# v3b_pcb.net
KiCad netlist of a schematic drawn in EAGLE
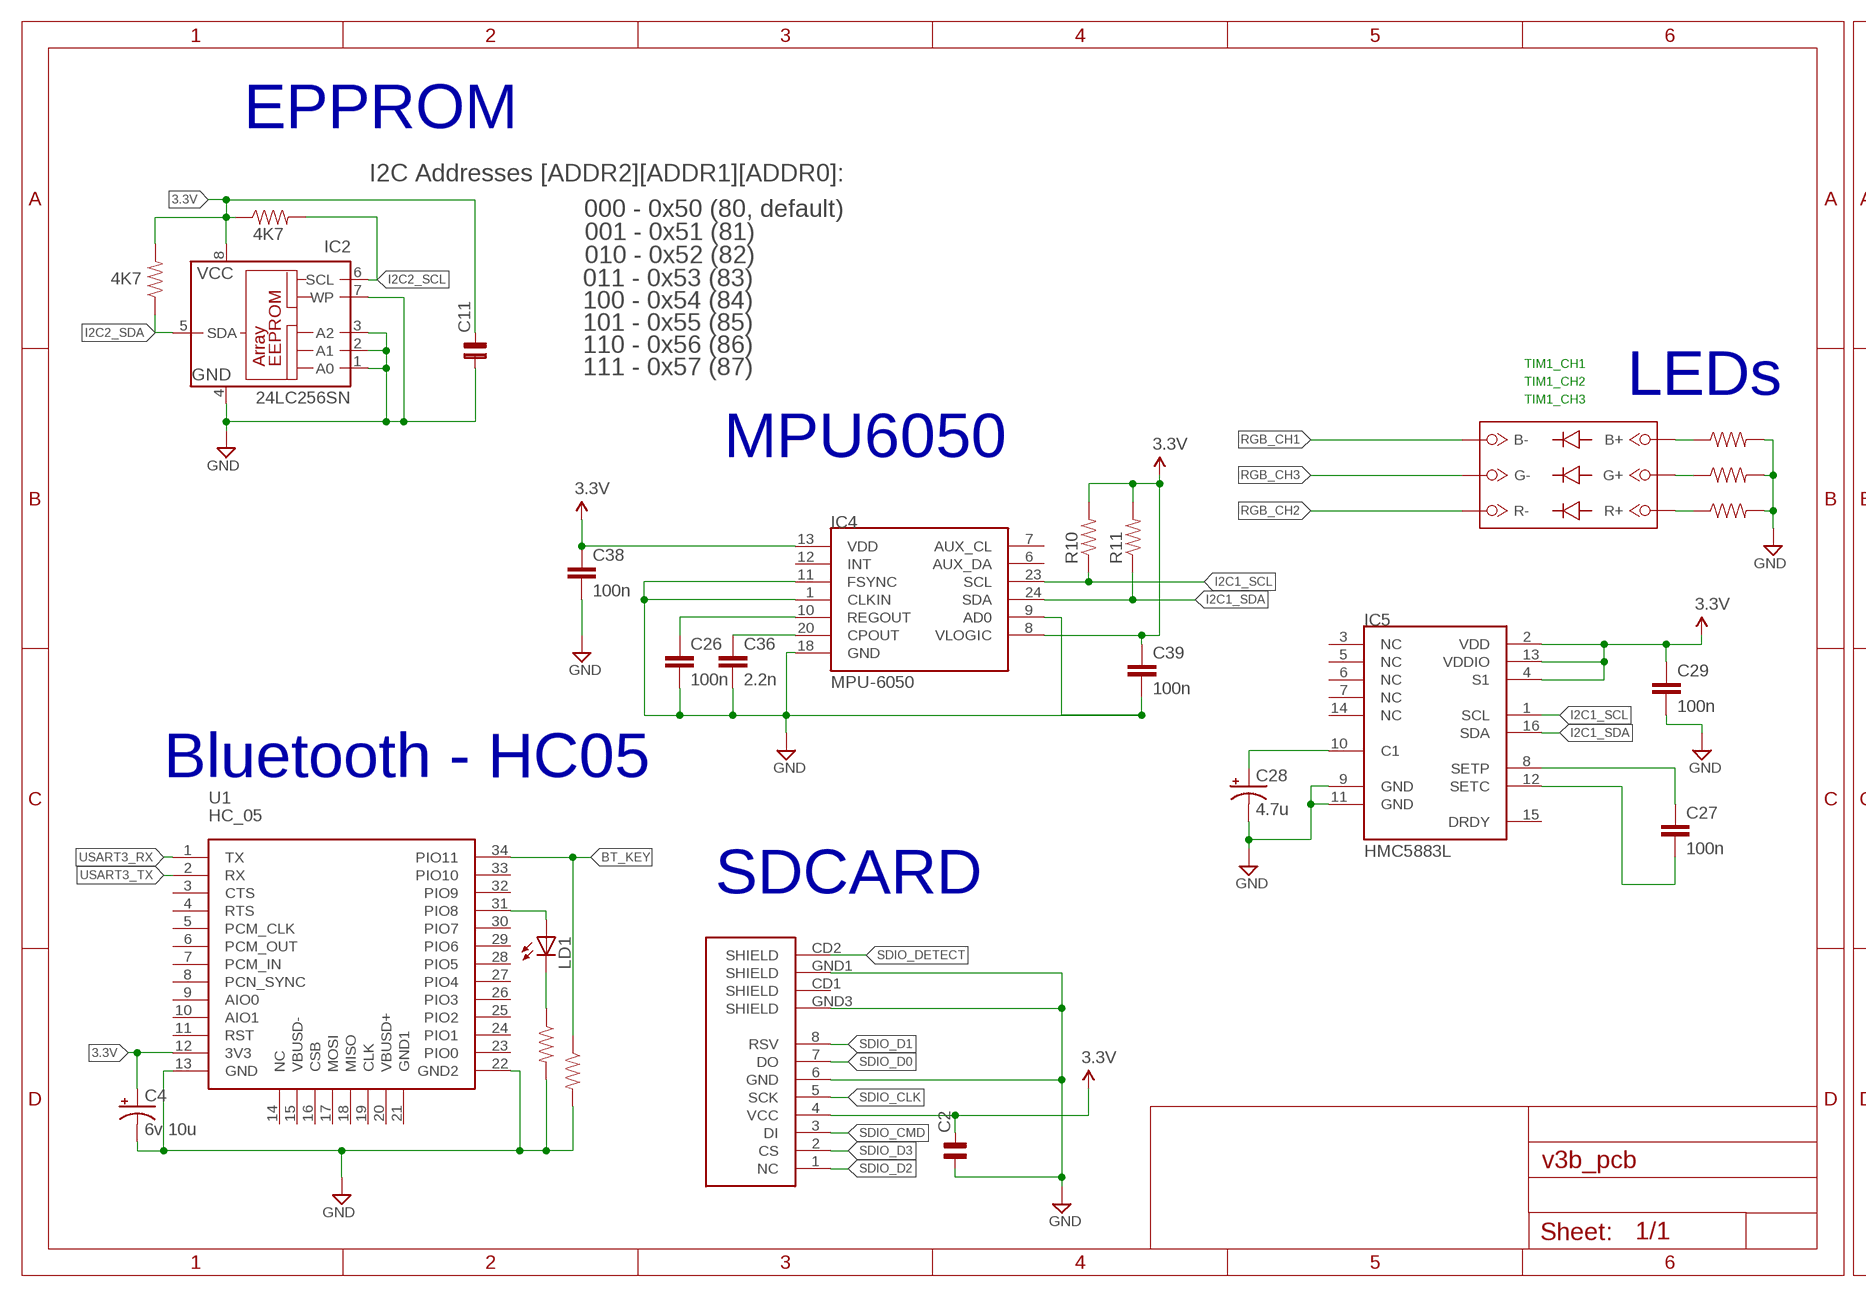
[diagram p0: schematic, sheet 1, part 1 of 2]
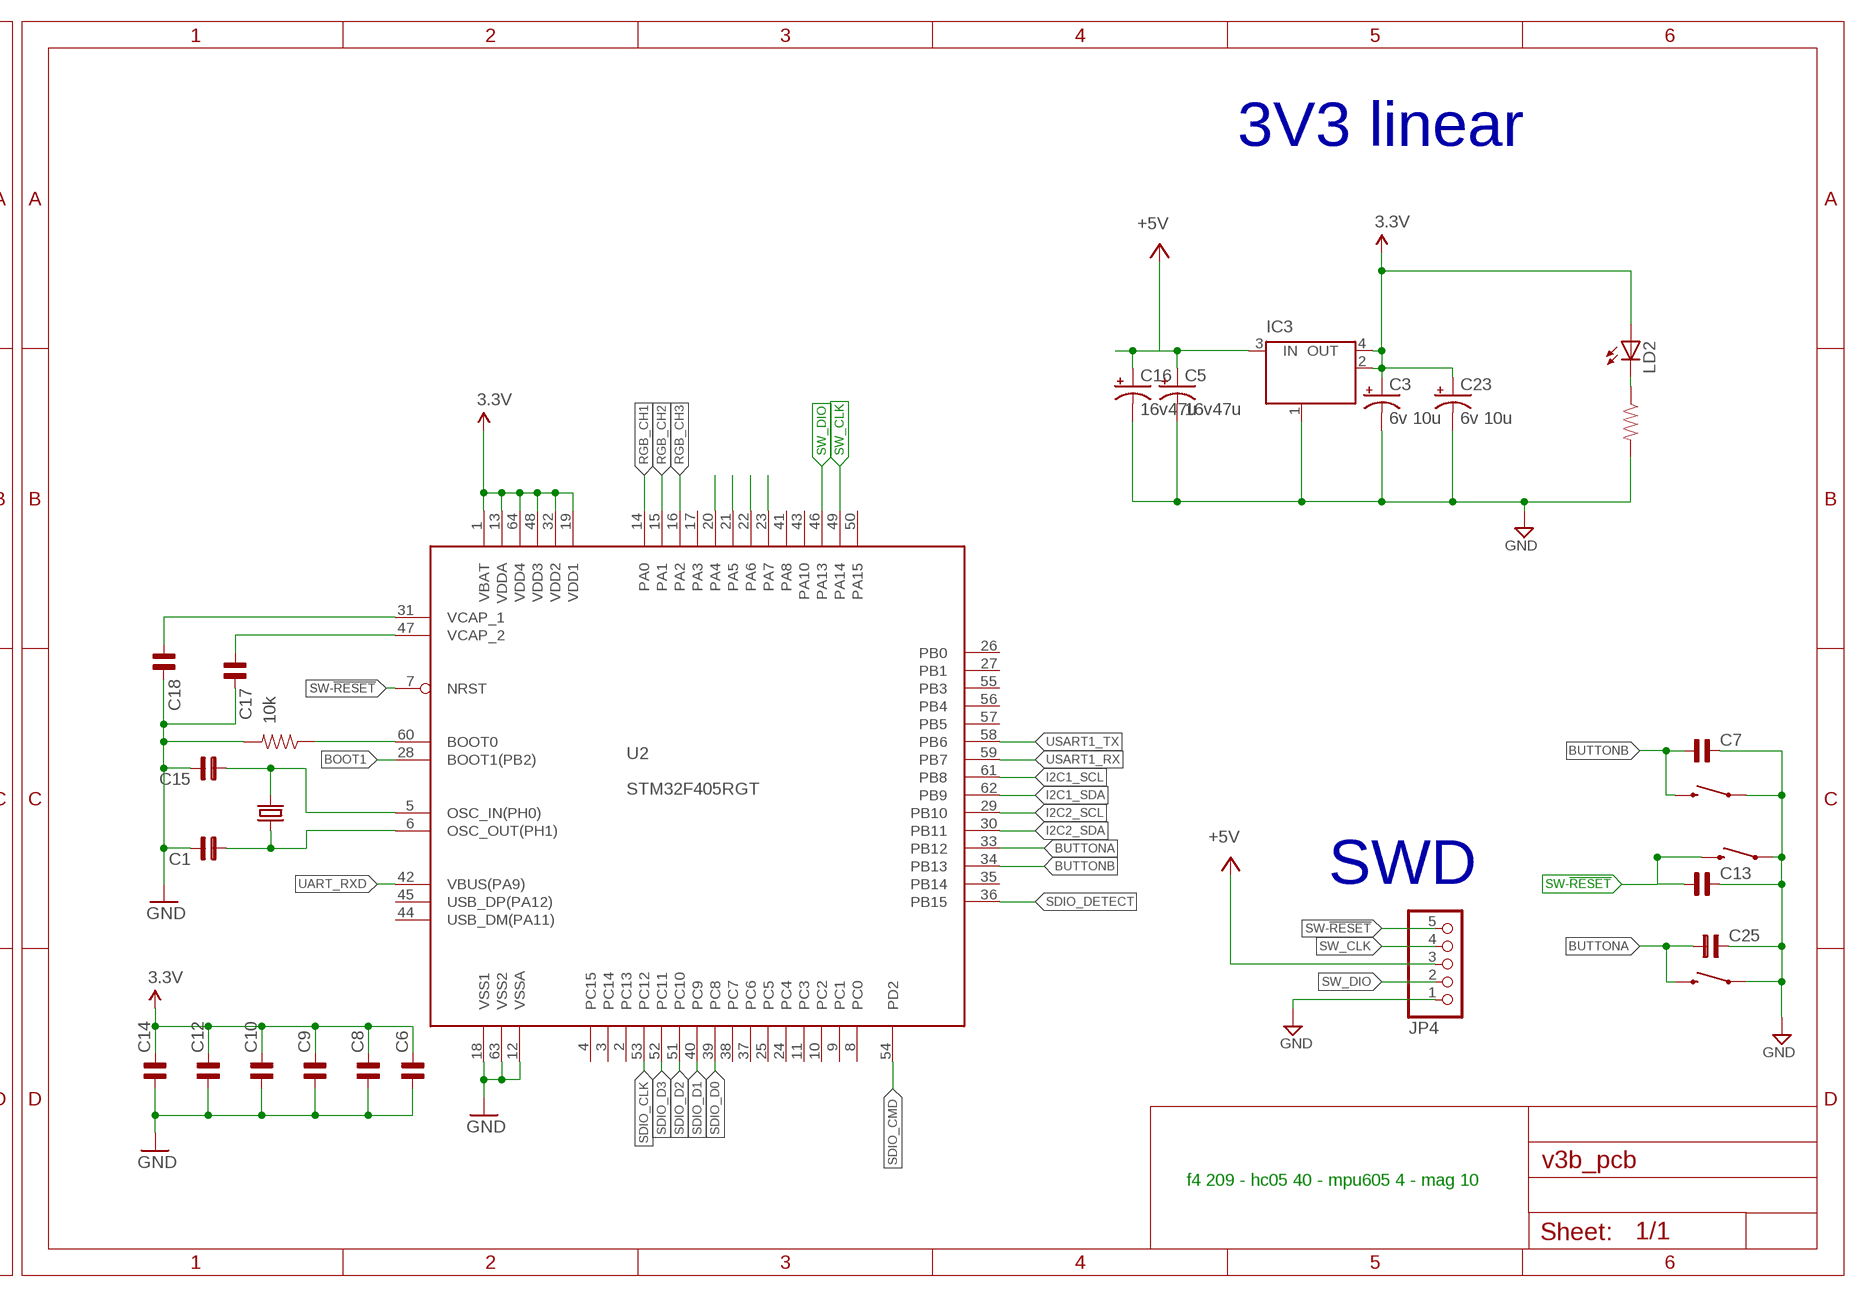
[diagram p1: schematic, sheet 1, part 2 of 2]

(export (version "E")
  (design (tool "Eeschema 10.0.6"))
  (components
    (comp (ref "C1")
      (value "C-NP-SMD-0603")
      (footprint "eagle-import:C-0603")
      (libsource (lib "eagle-import") (part "C-NP-SMD-0603"))
    )
    (comp (ref "C2")
      (value "C-NP-SMD-0603")
      (footprint "eagle-import:C-0603")
      (libsource (lib "eagle-import") (part "C-NP-SMD-0603"))
    )
    (comp (ref "C3")
      (value "6v 10u")
      (footprint "eagle-import:SMC_C")
      (libsource (lib "eagle-import") (part "CPOL-USSMCC"))
    )
    (comp (ref "C4")
      (value "6v 10u")
      (footprint "eagle-import:SMC_A")
      (libsource (lib "eagle-import") (part "CPOL-USSMCA"))
    )
    (comp (ref "C5")
      (value "16v47u")
      (footprint "eagle-import:SMC_C")
      (libsource (lib "eagle-import") (part "CPOL-USSMCC"))
    )
    (comp (ref "C6")
      (value "C-NP-SMD-0603")
      (footprint "eagle-import:C-0603")
      (libsource (lib "eagle-import") (part "C-NP-SMD-0603"))
    )
    (comp (ref "C7")
      (value "C-NP-SMD-0603")
      (footprint "eagle-import:C-0603")
      (libsource (lib "eagle-import") (part "C-NP-SMD-0603"))
    )
    (comp (ref "C8")
      (value "C-NP-SMD-0603")
      (footprint "eagle-import:C-0603")
      (libsource (lib "eagle-import") (part "C-NP-SMD-0603"))
    )
    (comp (ref "C9")
      (value "C-NP-SMD-0603")
      (footprint "eagle-import:C-0603")
      (libsource (lib "eagle-import") (part "C-NP-SMD-0603"))
    )
    (comp (ref "C10")
      (value "C-NP-SMD-0603")
      (footprint "eagle-import:C-0603")
      (libsource (lib "eagle-import") (part "C-NP-SMD-0603"))
    )
    (comp (ref "C11")
      (value "C-NP-SMD-0603")
      (footprint "eagle-import:C-0603")
      (libsource (lib "eagle-import") (part "C-NP-SMD-0603"))
    )
    (comp (ref "C12")
      (value "C-NP-SMD-0603")
      (footprint "eagle-import:C-0603")
      (libsource (lib "eagle-import") (part "C-NP-SMD-0603"))
    )
    (comp (ref "C13")
      (value "C-NP-SMD-0603")
      (footprint "eagle-import:C-0603")
      (libsource (lib "eagle-import") (part "C-NP-SMD-0603"))
    )
    (comp (ref "C14")
      (value "C-NP-SMD-0603")
      (footprint "eagle-import:C-0603")
      (libsource (lib "eagle-import") (part "C-NP-SMD-0603"))
    )
    (comp (ref "C15")
      (value "C-NP-SMD-0603")
      (footprint "eagle-import:C-0603")
      (libsource (lib "eagle-import") (part "C-NP-SMD-0603"))
    )
    (comp (ref "C16")
      (value "16v47u")
      (footprint "eagle-import:SMC_C")
      (libsource (lib "eagle-import") (part "CPOL-USSMCC"))
    )
    (comp (ref "C17")
      (value "C-NP-SMD-0603")
      (footprint "eagle-import:C-0603")
      (libsource (lib "eagle-import") (part "C-NP-SMD-0603"))
    )
    (comp (ref "C18")
      (value "C-NP-SMD-0603")
      (footprint "eagle-import:C-0603")
      (libsource (lib "eagle-import") (part "C-NP-SMD-0603"))
    )
    (comp (ref "C23")
      (value "6v 10u")
      (footprint "eagle-import:SMC_C")
      (libsource (lib "eagle-import") (part "CPOL-USSMCC"))
    )
    (comp (ref "C25")
      (value "C-NP-SMD-0603")
      (footprint "eagle-import:C-0603")
      (libsource (lib "eagle-import") (part "C-NP-SMD-0603"))
    )
    (comp (ref "C26")
      (value "100n")
      (footprint "eagle-import:SPARKFUN_0603-CAP")
      (libsource (lib "eagle-import") (part "SPARKFUN_CAP0603-CAP"))
    )
    (comp (ref "C27")
      (value "100n")
      (footprint "eagle-import:SPARKFUN_0603-CAP")
      (libsource (lib "eagle-import") (part "SPARKFUN_CAP0603-CAP"))
    )
    (comp (ref "C28")
      (value "4.7u")
      (footprint "eagle-import:SMC_A")
      (libsource (lib "eagle-import") (part "CPOL-USSMCA"))
    )
    (comp (ref "C29")
      (value "100n")
      (footprint "eagle-import:SPARKFUN_0603-CAP")
      (libsource (lib "eagle-import") (part "SPARKFUN_CAP0603-CAP"))
    )
    (comp (ref "C36")
      (value "2.2n")
      (footprint "eagle-import:SPARKFUN_0603-CAP")
      (libsource (lib "eagle-import") (part "SPARKFUN_CAP0603-CAP"))
    )
    (comp (ref "C38")
      (value "100n")
      (footprint "eagle-import:SPARKFUN_0603-CAP")
      (libsource (lib "eagle-import") (part "SPARKFUN_CAP0603-CAP"))
    )
    (comp (ref "C39")
      (value "100n")
      (footprint "eagle-import:SPARKFUN_0603-CAP")
      (libsource (lib "eagle-import") (part "SPARKFUN_CAP0603-CAP"))
    )
    (comp (ref "IC2")
      (value "24LC256SN")
      (footprint "eagle-import:SO-08")
      (fields (field (name "MF") "MICROCHIP") (field (name "MPN") "24LC256-I/SN"))
      (libsource (lib "eagle-import") (part "24SNLC256"))
    )
    (comp (ref "IC3")
      (value "LINEAR_MC33269ST-3.3T3")
      (footprint "eagle-import:LINEAR_SOT223")
      (libsource (lib "eagle-import") (part "LINEAR_MC33269ST-3.3T3"))
    )
    (comp (ref "IC4")
      (value "MPU-6050")
      (footprint "eagle-import:TESTING_QFN-24-4MM2")
      (libsource (lib "eagle-import") (part "TESTING_MPU-6050-1"))
    )
    (comp (ref "IC5")
      (value "HMC5883L")
      (footprint "eagle-import:SPARKFUN_16LPCC")
      (libsource (lib "eagle-import") (part "SPARKFUN_HMC5883LSMD"))
    )
    (comp (ref "JP4")
      (value "PINHD-1X5_2.54-90°")
      (footprint "eagle-import:1X05_90")
      (libsource (lib "eagle-import") (part "PINHD-1X5_2.54-90°"))
    )
    (comp (ref "LD1")
      (value "LEDCHIPLED_0603")
      (footprint "eagle-import:CHIPLED_0603")
      (libsource (lib "eagle-import") (part "LEDCHIPLED_0603"))
    )
    (comp (ref "LD2")
      (value "LEDCHIPLED_0603")
      (footprint "eagle-import:CHIPLED_0603")
      (libsource (lib "eagle-import") (part "LEDCHIPLED_0603"))
    )
    (comp (ref "R1")
      (value "10K")
      (footprint "eagle-import:SPARKFUN_0603-RES")
      (libsource (lib "eagle-import") (part "Robotech_RCL_SPARKFUN_RESISTOR0603-RES"))
    )
    (comp (ref "R2")
      (value "10K")
      (footprint "eagle-import:SPARKFUN_0603-RES")
      (libsource (lib "eagle-import") (part "Robotech_RCL_SPARKFUN_RESISTOR0603-RES"))
    )
    (comp (ref "R3")
      (value "10K")
      (footprint "eagle-import:SPARKFUN_0603-RES")
      (libsource (lib "eagle-import") (part "Robotech_RCL_SPARKFUN_RESISTOR0603-RES"))
    )
    (comp (ref "R5")
      (value "10K")
      (footprint "eagle-import:SPARKFUN_0603-RES")
      (libsource (lib "eagle-import") (part "Robotech_RCL_SPARKFUN_RESISTOR0603-RES"))
    )
    (comp (ref "R6")
      (value "10K")
      (footprint "eagle-import:SPARKFUN_0603-RES")
      (libsource (lib "eagle-import") (part "Robotech_RCL_SPARKFUN_RESISTOR0603-RES"))
    )
    (comp (ref "R7")
      (value "10k")
      (footprint "eagle-import:SPARKFUN_0603-RES")
      (libsource (lib "eagle-import") (part "Robotech_RCL_SPARKFUN_RESISTOR0603-RES"))
    )
    (comp (ref "R9")
      (value "10K")
      (footprint "eagle-import:SPARKFUN_0603-RES")
      (libsource (lib "eagle-import") (part "Robotech_RCL_SPARKFUN_RESISTOR0603-RES"))
    )
    (comp (ref "R10")
      (value "SPARKFUN_RESISTOR0603-RES")
      (footprint "eagle-import:SPARKFUN_0603-RES")
      (libsource (lib "eagle-import") (part "SPARKFUN_RESISTOR0603-RES"))
    )
    (comp (ref "R11")
      (value "SPARKFUN_RESISTOR0603-RES")
      (footprint "eagle-import:SPARKFUN_0603-RES")
      (libsource (lib "eagle-import") (part "SPARKFUN_RESISTOR0603-RES"))
    )
    (comp (ref "R15")
      (value "4K7")
      (footprint "eagle-import:SPARKFUN_0603-RES")
      (libsource (lib "eagle-import") (part "Robotech_RCL_SPARKFUN_RESISTOR0603-RES"))
    )
    (comp (ref "R16")
      (value "4K7")
      (footprint "eagle-import:SPARKFUN_0603-RES")
      (libsource (lib "eagle-import") (part "Robotech_RCL_SPARKFUN_RESISTOR0603-RES"))
    )
    (comp (ref "S1")
      (value "RESET")
      (footprint "eagle-import:TACTILE-SWITCH-1101NE")
      (fields (field (name "PARTNO") "EVQ-P7J01P"))
      (libsource (lib "eagle-import") (part "SWITCH-MOMENTARY-2-SMD-1101NE"))
    )
    (comp (ref "S2")
      (value "RESET")
      (footprint "eagle-import:TACTILE-SWITCH-1101NE")
      (fields (field (name "PARTNO") "EVQ-P7J01P"))
      (libsource (lib "eagle-import") (part "SWITCH-MOMENTARY-2-SMD-1101NE"))
    )
    (comp (ref "S4")
      (value "RESET")
      (footprint "eagle-import:TACTILE-SWITCH-1101NE")
      (fields (field (name "PARTNO") "EVQ-P7J01P"))
      (libsource (lib "eagle-import") (part "SWITCH-MOMENTARY-2-SMD-1101NE"))
    )
    (comp (ref "SDCARD2")
      (value "microSD Socket")
      (footprint "eagle-import:MICRO-SD-SOCKET-PP")
      (libsource (lib "eagle-import") (part "USD-SOCKETNEW"))
    )
    (comp (ref "U$12")
      (value "RGB_LED")
      (footprint "eagle-import:SMD")
      (libsource (lib "eagle-import") (part "RGB_LED"))
    )
    (comp (ref "U1")
      (value "HC_05")
      (footprint "eagle-import:BLUETOOTH_SMD")
      (libsource (lib "eagle-import") (part "HC_05"))
    )
    (comp (ref "U2")
      (value "STM32F405RGT")
      (footprint "eagle-import:LQFP64")
      (libsource (lib "eagle-import") (part "STM32F405RGT"))
    )
    (comp (ref "Y2")
      (value "CRYSTALHC49US")
      (footprint "eagle-import:HC49US")
      (libsource (lib "eagle-import") (part "CRYSTALHC49US"))
    )
  )
  (nets
    (net (code "1") (name "+5V") (class "Default")
      (node (ref "C16") (pin "+") (pinfunction "+_+") (pintype "passive"))
      (node (ref "C5") (pin "+") (pinfunction "+_+") (pintype "passive"))
      (node (ref "IC3") (pin "3") (pinfunction "IN_3") (pintype "input"))
      (node (ref "JP4") (pin "3") (pinfunction "3_3") (pintype "passive"))
    )
    (net (code "2") (name "/SW-~{RESET}") (class "Default")
      (node (ref "C13") (pin "1") (pinfunction "1_1") (pintype "passive"))
      (node (ref "JP4") (pin "5") (pinfunction "5_5") (pintype "passive"))
      (node (ref "S1") (pin "P$2") (pinfunction "2_P$2") (pintype "passive"))
      (node (ref "U2") (pin "7") (pinfunction "NRST_7") (pintype "input"))
    )
    (net (code "3") (name "3.3V") (class "Default")
      (node (ref "C10") (pin "2") (pinfunction "2_2") (pintype "passive"))
      (node (ref "C11") (pin "2") (pinfunction "2_2") (pintype "passive"))
      (node (ref "C12") (pin "2") (pinfunction "2_2") (pintype "passive"))
      (node (ref "C14") (pin "2") (pinfunction "2_2") (pintype "passive"))
      (node (ref "C2") (pin "2") (pinfunction "2_2") (pintype "passive"))
      (node (ref "C23") (pin "+") (pinfunction "+_+") (pintype "passive"))
      (node (ref "C29") (pin "1") (pinfunction "1_1") (pintype "passive"))
      (node (ref "C3") (pin "+") (pinfunction "+_+") (pintype "passive"))
      (node (ref "C38") (pin "1") (pinfunction "1_1") (pintype "passive"))
      (node (ref "C39") (pin "1") (pinfunction "1_1") (pintype "passive"))
      (node (ref "C4") (pin "+") (pinfunction "+_+") (pintype "passive"))
      (node (ref "C6") (pin "2") (pinfunction "2_2") (pintype "passive"))
      (node (ref "C8") (pin "2") (pinfunction "2_2") (pintype "passive"))
      (node (ref "C9") (pin "2") (pinfunction "2_2") (pintype "passive"))
      (node (ref "IC2") (pin "8") (pinfunction "VCC_8") (pintype "power_in"))
      (node (ref "IC3") (pin "2") (pinfunction "OUT_2") (pintype "passive"))
      (node (ref "IC3") (pin "4") (pinfunction "OUT_4") (pintype "passive"))
      (node (ref "IC4") (pin "13") (pinfunction "VDD_13") (pintype "bidirectional"))
      (node (ref "IC4") (pin "8") (pinfunction "VLOGIC_8") (pintype "bidirectional"))
      (node (ref "IC5") (pin "13") (pinfunction "VDDIO_13") (pintype "bidirectional"))
      (node (ref "IC5") (pin "2") (pinfunction "VDD_2") (pintype "bidirectional"))
      (node (ref "IC5") (pin "4") (pinfunction "S1_4") (pintype "bidirectional"))
      (node (ref "LD2") (pin "A") (pinfunction "A_A") (pintype "passive"))
      (node (ref "R10") (pin "2") (pinfunction "2_2") (pintype "passive"))
      (node (ref "R11") (pin "2") (pinfunction "2_2") (pintype "passive"))
      (node (ref "R15") (pin "1") (pinfunction "1_1") (pintype "passive"))
      (node (ref "R16") (pin "2") (pinfunction "2_2") (pintype "passive"))
      (node (ref "SDCARD2") (pin "4") (pinfunction "VCC_4") (pintype "bidirectional"))
      (node (ref "U1") (pin "12") (pinfunction "3V3_12") (pintype "bidirectional"))
      (node (ref "U2") (pin "1") (pinfunction "VBAT_1") (pintype "power_in"))
      (node (ref "U2") (pin "13") (pinfunction "VDDA_13") (pintype "power_in"))
      (node (ref "U2") (pin "19") (pinfunction "VDD1_19") (pintype "power_in"))
      (node (ref "U2") (pin "32") (pinfunction "VDD2_32") (pintype "power_in"))
      (node (ref "U2") (pin "48") (pinfunction "VDD3_48") (pintype "power_in"))
      (node (ref "U2") (pin "64") (pinfunction "VDD4_64") (pintype "power_in"))
    )
    (net (code "4") (name "BOOT1") (class "Default")
      (node (ref "U2") (pin "28") (pinfunction "BOOT1(PB2)_28") (pintype "input"))
    )
    (net (code "5") (name "BT_KEY") (class "Default")
      (node (ref "R5") (pin "1") (pinfunction "1_1") (pintype "passive"))
      (node (ref "U1") (pin "34") (pinfunction "PIO11_34") (pintype "bidirectional"))
    )
    (net (code "6") (name "BUTTONA") (class "Default")
      (node (ref "C25") (pin "1") (pinfunction "1_1") (pintype "passive"))
      (node (ref "S2") (pin "P$2") (pinfunction "2_P$2") (pintype "passive"))
      (node (ref "U2") (pin "33") (pinfunction "PB12_33") (pintype "bidirectional"))
    )
    (net (code "7") (name "BUTTONB") (class "Default")
      (node (ref "C7") (pin "1") (pinfunction "1_1") (pintype "passive"))
      (node (ref "S4") (pin "P$2") (pinfunction "2_P$2") (pintype "passive"))
      (node (ref "U2") (pin "34") (pinfunction "PB13_34") (pintype "bidirectional"))
    )
    (net (code "8") (name "GND") (class "Default")
      (node (ref "C1") (pin "2") (pinfunction "2_2") (pintype "passive"))
      (node (ref "C10") (pin "1") (pinfunction "1_1") (pintype "passive"))
      (node (ref "C11") (pin "1") (pinfunction "1_1") (pintype "passive"))
      (node (ref "C12") (pin "1") (pinfunction "1_1") (pintype "passive"))
      (node (ref "C13") (pin "2") (pinfunction "2_2") (pintype "passive"))
      (node (ref "C14") (pin "1") (pinfunction "1_1") (pintype "passive"))
      (node (ref "C15") (pin "2") (pinfunction "2_2") (pintype "passive"))
      (node (ref "C16") (pin "-") (pinfunction "-_-") (pintype "passive"))
      (node (ref "C17") (pin "2") (pinfunction "2_2") (pintype "passive"))
      (node (ref "C18") (pin "2") (pinfunction "2_2") (pintype "passive"))
      (node (ref "C2") (pin "1") (pinfunction "1_1") (pintype "passive"))
      (node (ref "C23") (pin "-") (pinfunction "-_-") (pintype "passive"))
      (node (ref "C25") (pin "2") (pinfunction "2_2") (pintype "passive"))
      (node (ref "C26") (pin "2") (pinfunction "2_2") (pintype "passive"))
      (node (ref "C28") (pin "-") (pinfunction "-_-") (pintype "passive"))
      (node (ref "C29") (pin "2") (pinfunction "2_2") (pintype "passive"))
      (node (ref "C3") (pin "-") (pinfunction "-_-") (pintype "passive"))
      (node (ref "C36") (pin "2") (pinfunction "2_2") (pintype "passive"))
      (node (ref "C38") (pin "2") (pinfunction "2_2") (pintype "passive"))
      (node (ref "C39") (pin "2") (pinfunction "2_2") (pintype "passive"))
      (node (ref "C4") (pin "-") (pinfunction "-_-") (pintype "passive"))
      (node (ref "C5") (pin "-") (pinfunction "-_-") (pintype "passive"))
      (node (ref "C6") (pin "1") (pinfunction "1_1") (pintype "passive"))
      (node (ref "C7") (pin "2") (pinfunction "2_2") (pintype "passive"))
      (node (ref "C8") (pin "1") (pinfunction "1_1") (pintype "passive"))
      (node (ref "C9") (pin "1") (pinfunction "1_1") (pintype "passive"))
      (node (ref "IC2") (pin "1") (pinfunction "A0_1") (pintype "input"))
      (node (ref "IC2") (pin "2") (pinfunction "A1_2") (pintype "input"))
      (node (ref "IC2") (pin "3") (pinfunction "A2_3") (pintype "input"))
      (node (ref "IC2") (pin "4") (pinfunction "GND_4") (pintype "power_in"))
      (node (ref "IC2") (pin "7") (pinfunction "WP_7") (pintype "input"))
      (node (ref "IC3") (pin "1") (pinfunction "GND/ADJ_1") (pintype "input"))
      (node (ref "IC4") (pin "1") (pinfunction "CLKIN_1") (pintype "bidirectional"))
      (node (ref "IC4") (pin "11") (pinfunction "FSYNC_11") (pintype "bidirectional"))
      (node (ref "IC4") (pin "18") (pinfunction "GND_18") (pintype "bidirectional"))
      (node (ref "IC4") (pin "9") (pinfunction "AD0_9") (pintype "bidirectional"))
      (node (ref "IC5") (pin "11") (pinfunction "GND_11") (pintype "bidirectional"))
      (node (ref "IC5") (pin "9") (pinfunction "GND_9") (pintype "bidirectional"))
      (node (ref "JP4") (pin "1") (pinfunction "1_1") (pintype "passive"))
      (node (ref "R1") (pin "2") (pinfunction "2_2") (pintype "passive"))
      (node (ref "R2") (pin "2") (pinfunction "2_2") (pintype "passive"))
      (node (ref "R3") (pin "2") (pinfunction "2_2") (pintype "passive"))
      (node (ref "R5") (pin "2") (pinfunction "2_2") (pintype "passive"))
      (node (ref "R6") (pin "2") (pinfunction "2_2") (pintype "passive"))
      (node (ref "R7") (pin "2") (pinfunction "2_2") (pintype "passive"))
      (node (ref "R9") (pin "2") (pinfunction "2_2") (pintype "passive"))
      (node (ref "S1") (pin "P$1") (pinfunction "1_P$1") (pintype "passive"))
      (node (ref "S2") (pin "P$1") (pinfunction "1_P$1") (pintype "passive"))
      (node (ref "S4") (pin "P$1") (pinfunction "1_P$1") (pintype "passive"))
      (node (ref "SDCARD2") (pin "6") (pinfunction "GND_6") (pintype "bidirectional"))
      (node (ref "SDCARD2") (pin "GND1") (pinfunction "SHIELD_GND1") (pintype "bidirectional"))
      (node (ref "SDCARD2") (pin "GND3") (pinfunction "SHIELD_GND3") (pintype "bidirectional"))
      (node (ref "U1") (pin "13") (pinfunction "GND_13") (pintype "bidirectional"))
      (node (ref "U1") (pin "22") (pinfunction "GND2_22") (pintype "bidirectional"))
      (node (ref "U2") (pin "12") (pinfunction "VSSA_12") (pintype "power_in"))
      (node (ref "U2") (pin "18") (pinfunction "VSS1_18") (pintype "power_in"))
      (node (ref "U2") (pin "63") (pinfunction "VSS2_63") (pintype "power_in"))
    )
    (net (code "9") (name "I2C1_SCL") (class "Default")
      (node (ref "IC4") (pin "23") (pinfunction "SCL_23") (pintype "bidirectional"))
      (node (ref "IC5") (pin "1") (pinfunction "SCL_1") (pintype "bidirectional"))
      (node (ref "R10") (pin "1") (pinfunction "1_1") (pintype "passive"))
      (node (ref "U2") (pin "61") (pinfunction "PB8_61") (pintype "bidirectional"))
    )
    (net (code "10") (name "I2C1_SDA") (class "Default")
      (node (ref "IC4") (pin "24") (pinfunction "SDA_24") (pintype "bidirectional"))
      (node (ref "IC5") (pin "16") (pinfunction "SDA_16") (pintype "bidirectional"))
      (node (ref "R11") (pin "1") (pinfunction "1_1") (pintype "passive"))
      (node (ref "U2") (pin "62") (pinfunction "PB9_62") (pintype "bidirectional"))
    )
    (net (code "11") (name "I2C2_SCL") (class "Default")
      (node (ref "IC2") (pin "6") (pinfunction "SCL_6") (pintype "input"))
      (node (ref "R15") (pin "2") (pinfunction "2_2") (pintype "passive"))
      (node (ref "U2") (pin "29") (pinfunction "PB10_29") (pintype "bidirectional"))
    )
    (net (code "12") (name "I2C2_SDA") (class "Default")
      (node (ref "IC2") (pin "5") (pinfunction "SDA_5") (pintype "bidirectional"))
      (node (ref "R16") (pin "1") (pinfunction "1_1") (pintype "passive"))
      (node (ref "U2") (pin "30") (pinfunction "PB11_30") (pintype "bidirectional"))
    )
    (net (code "13") (name "Net-(IC4-CPOUT)") (class "Default")
      (node (ref "C36") (pin "1") (pinfunction "1_1") (pintype "passive"))
      (node (ref "IC4") (pin "20") (pinfunction "CPOUT_20") (pintype "bidirectional"))
    )
    (net (code "14") (name "Net-(IC4-REGOUT)") (class "Default")
      (node (ref "C26") (pin "1") (pinfunction "1_1") (pintype "passive"))
      (node (ref "IC4") (pin "10") (pinfunction "REGOUT_10") (pintype "bidirectional"))
    )
    (net (code "15") (name "Net-(IC5-C1)") (class "Default")
      (node (ref "C28") (pin "+") (pinfunction "+_+") (pintype "passive"))
      (node (ref "IC5") (pin "10") (pinfunction "C1_10") (pintype "bidirectional"))
    )
    (net (code "16") (name "Net-(IC5-SETC)") (class "Default")
      (node (ref "C27") (pin "2") (pinfunction "2_2") (pintype "passive"))
      (node (ref "IC5") (pin "12") (pinfunction "SETC_12") (pintype "bidirectional"))
    )
    (net (code "17") (name "Net-(IC5-SETP)") (class "Default")
      (node (ref "C27") (pin "1") (pinfunction "1_1") (pintype "passive"))
      (node (ref "IC5") (pin "8") (pinfunction "SETP_8") (pintype "bidirectional"))
    )
    (net (code "18") (name "Net-(LD1-PadC)") (class "Default")
      (node (ref "LD1") (pin "C") (pinfunction "C_C") (pintype "passive"))
      (node (ref "R9") (pin "1") (pinfunction "1_1") (pintype "passive"))
    )
    (net (code "19") (name "Net-(LD2-PadC)") (class "Default")
      (node (ref "LD2") (pin "C") (pinfunction "C_C") (pintype "passive"))
      (node (ref "R1") (pin "1") (pinfunction "1_1") (pintype "passive"))
    )
    (net (code "20") (name "Net-(R2-Pad1)") (class "Default")
      (node (ref "R2") (pin "1") (pinfunction "1_1") (pintype "passive"))
      (node (ref "U$12") (pin "B+") (pinfunction "B+_B+") (pintype "bidirectional"))
    )
    (net (code "21") (name "Net-(R3-Pad1)") (class "Default")
      (node (ref "R3") (pin "1") (pinfunction "1_1") (pintype "passive"))
      (node (ref "U$12") (pin "G+") (pinfunction "G+_G+") (pintype "bidirectional"))
    )
    (net (code "22") (name "Net-(R6-Pad1)") (class "Default")
      (node (ref "R6") (pin "1") (pinfunction "1_1") (pintype "passive"))
      (node (ref "U$12") (pin "R+") (pinfunction "R+_R+") (pintype "bidirectional"))
    )
    (net (code "23") (name "Net-(U1-PIO8)") (class "Default")
      (node (ref "LD1") (pin "A") (pinfunction "A_A") (pintype "passive"))
      (node (ref "U1") (pin "31") (pinfunction "PIO8_31") (pintype "bidirectional"))
    )
    (net (code "24") (name "Net-(U2-BOOT0)") (class "Default")
      (node (ref "R7") (pin "1") (pinfunction "1_1") (pintype "passive"))
      (node (ref "U2") (pin "60") (pinfunction "BOOT0_60") (pintype "input"))
    )
    (net (code "25") (name "Net-(U2-OSC_IN(PH0))") (class "Default")
      (node (ref "C15") (pin "1") (pinfunction "1_1") (pintype "passive"))
      (node (ref "U2") (pin "5") (pinfunction "OSC_IN(PH0)_5") (pintype "bidirectional"))
      (node (ref "Y2") (pin "2") (pinfunction "2_2") (pintype "passive"))
    )
    (net (code "26") (name "Net-(U2-OSC_OUT(PH1))") (class "Default")
      (node (ref "C1") (pin "1") (pinfunction "1_1") (pintype "passive"))
      (node (ref "U2") (pin "6") (pinfunction "OSC_OUT(PH1)_6") (pintype "bidirectional"))
      (node (ref "Y2") (pin "1") (pinfunction "1_1") (pintype "passive"))
    )
    (net (code "27") (name "Net-(U2-VCAP_1)") (class "Default")
      (node (ref "C18") (pin "1") (pinfunction "1_1") (pintype "passive"))
      (node (ref "U2") (pin "31") (pinfunction "VCAP_1_31") (pintype "bidirectional"))
    )
    (net (code "28") (name "Net-(U2-VCAP_2)") (class "Default")
      (node (ref "C17") (pin "1") (pinfunction "1_1") (pintype "passive"))
      (node (ref "U2") (pin "47") (pinfunction "VCAP_2_47") (pintype "bidirectional"))
    )
    (net (code "29") (name "RGB_CH1") (class "Default")
      (node (ref "U$12") (pin "B-") (pinfunction "B-_B-") (pintype "bidirectional"))
      (node (ref "U2") (pin "14") (pinfunction "PA0_14") (pintype "bidirectional"))
    )
    (net (code "30") (name "RGB_CH2") (class "Default")
      (node (ref "U$12") (pin "R-") (pinfunction "R-_R-") (pintype "bidirectional"))
      (node (ref "U2") (pin "15") (pinfunction "PA1_15") (pintype "bidirectional"))
    )
    (net (code "31") (name "RGB_CH3") (class "Default")
      (node (ref "U$12") (pin "G-") (pinfunction "G-_G-") (pintype "bidirectional"))
      (node (ref "U2") (pin "16") (pinfunction "PA2_16") (pintype "bidirectional"))
    )
    (net (code "32") (name "SDIO_CLK") (class "Default")
      (node (ref "SDCARD2") (pin "5") (pinfunction "SCK_5") (pintype "bidirectional"))
      (node (ref "U2") (pin "53") (pinfunction "PC12_53") (pintype "bidirectional"))
    )
    (net (code "33") (name "SDIO_CMD") (class "Default")
      (node (ref "SDCARD2") (pin "3") (pinfunction "DI_3") (pintype "bidirectional"))
      (node (ref "U2") (pin "54") (pinfunction "PD2_54") (pintype "bidirectional"))
    )
    (net (code "34") (name "SDIO_D0") (class "Default")
      (node (ref "SDCARD2") (pin "7") (pinfunction "DO_7") (pintype "bidirectional"))
      (node (ref "U2") (pin "39") (pinfunction "PC8_39") (pintype "bidirectional"))
    )
    (net (code "35") (name "SDIO_D1") (class "Default")
      (node (ref "SDCARD2") (pin "8") (pinfunction "RSV_8") (pintype "bidirectional"))
      (node (ref "U2") (pin "40") (pinfunction "PC9_40") (pintype "bidirectional"))
    )
    (net (code "36") (name "SDIO_D2") (class "Default")
      (node (ref "SDCARD2") (pin "1") (pinfunction "NC_1") (pintype "bidirectional"))
      (node (ref "U2") (pin "51") (pinfunction "PC10_51") (pintype "bidirectional"))
    )
    (net (code "37") (name "SDIO_D3") (class "Default")
      (node (ref "SDCARD2") (pin "2") (pinfunction "CS_2") (pintype "bidirectional"))
      (node (ref "U2") (pin "52") (pinfunction "PC11_52") (pintype "bidirectional"))
    )
    (net (code "38") (name "SDIO_DETECT") (class "Default")
      (node (ref "SDCARD2") (pin "CD2") (pinfunction "SHIELD_CD2") (pintype "bidirectional"))
      (node (ref "U2") (pin "36") (pinfunction "PB15_36") (pintype "bidirectional"))
    )
    (net (code "39") (name "SW_CLK") (class "Default")
      (node (ref "JP4") (pin "4") (pinfunction "4_4") (pintype "passive"))
      (node (ref "U2") (pin "49") (pinfunction "PA14_49") (pintype "bidirectional"))
    )
    (net (code "40") (name "SW_DIO") (class "Default")
      (node (ref "JP4") (pin "2") (pinfunction "2_2") (pintype "passive"))
      (node (ref "U2") (pin "46") (pinfunction "PA13_46") (pintype "bidirectional"))
    )
    (net (code "41") (name "UART_RXD") (class "Default")
      (node (ref "U2") (pin "42") (pinfunction "VBUS(PA9)_42") (pintype "bidirectional"))
    )
    (net (code "42") (name "USART1_RX") (class "Default")
      (node (ref "U2") (pin "59") (pinfunction "PB7_59") (pintype "bidirectional"))
    )
    (net (code "43") (name "USART1_TX") (class "Default")
      (node (ref "U2") (pin "58") (pinfunction "PB6_58") (pintype "bidirectional"))
    )
    (net (code "44") (name "USART3_RX") (class "Default")
      (node (ref "U1") (pin "1") (pinfunction "TX_1") (pintype "bidirectional"))
    )
    (net (code "45") (name "USART3_TX") (class "Default")
      (node (ref "U1") (pin "2") (pinfunction "RX_2") (pintype "bidirectional"))
    )
    (net (code "46") (name "unconnected-(IC4-AUX_CL-Pad7)") (class "Default")
      (node (ref "IC4") (pin "7") (pinfunction "AUX_CL_7") (pintype "bidirectional"))
    )
    (net (code "47") (name "unconnected-(IC4-AUX_DA-Pad6)") (class "Default")
      (node (ref "IC4") (pin "6") (pinfunction "AUX_DA_6") (pintype "bidirectional"))
    )
    (net (code "48") (name "unconnected-(IC4-INT-Pad12)") (class "Default")
      (node (ref "IC4") (pin "12") (pinfunction "INT_12") (pintype "bidirectional"))
    )
    (net (code "49") (name "unconnected-(IC5-DRDY-Pad15)") (class "Default")
      (node (ref "IC5") (pin "15") (pinfunction "DRDY_15") (pintype "bidirectional"))
    )
    (net (code "50") (name "unconnected-(IC5-NC-Pad3)") (class "Default")
      (node (ref "IC5") (pin "3") (pinfunction "NC_3") (pintype "bidirectional"))
    )
    (net (code "51") (name "unconnected-(IC5-NC-Pad5)") (class "Default")
      (node (ref "IC5") (pin "5") (pinfunction "NC_5") (pintype "bidirectional"))
    )
    (net (code "52") (name "unconnected-(IC5-NC-Pad6)") (class "Default")
      (node (ref "IC5") (pin "6") (pinfunction "NC_6") (pintype "bidirectional"))
    )
    (net (code "53") (name "unconnected-(IC5-NC-Pad7)") (class "Default")
      (node (ref "IC5") (pin "7") (pinfunction "NC_7") (pintype "bidirectional"))
    )
    (net (code "54") (name "unconnected-(IC5-NC-Pad14)") (class "Default")
      (node (ref "IC5") (pin "14") (pinfunction "NC_14") (pintype "bidirectional"))
    )
    (net (code "55") (name "unconnected-(SDCARD2-SHIELD-PadCD1)") (class "Default")
      (node (ref "SDCARD2") (pin "CD1") (pinfunction "SHIELD_CD1") (pintype "bidirectional"))
    )
    (net (code "56") (name "unconnected-(U1-AIO0-Pad9)") (class "Default")
      (node (ref "U1") (pin "9") (pinfunction "AIO0_9") (pintype "bidirectional"))
    )
    (net (code "57") (name "unconnected-(U1-AIO1-Pad10)") (class "Default")
      (node (ref "U1") (pin "10") (pinfunction "AIO1_10") (pintype "bidirectional"))
    )
    (net (code "58") (name "unconnected-(U1-CLK-Pad19)") (class "Default")
      (node (ref "U1") (pin "19") (pinfunction "CLK_19") (pintype "bidirectional"))
    )
    (net (code "59") (name "unconnected-(U1-CSB-Pad16)") (class "Default")
      (node (ref "U1") (pin "16") (pinfunction "CSB_16") (pintype "bidirectional"))
    )
    (net (code "60") (name "unconnected-(U1-CTS-Pad3)") (class "Default")
      (node (ref "U1") (pin "3") (pinfunction "CTS_3") (pintype "bidirectional"))
    )
    (net (code "61") (name "unconnected-(U1-GND1-Pad21)") (class "Default")
      (node (ref "U1") (pin "21") (pinfunction "GND1_21") (pintype "bidirectional"))
    )
    (net (code "62") (name "unconnected-(U1-MISO-Pad18)") (class "Default")
      (node (ref "U1") (pin "18") (pinfunction "MISO_18") (pintype "bidirectional"))
    )
    (net (code "63") (name "unconnected-(U1-MOSI-Pad17)") (class "Default")
      (node (ref "U1") (pin "17") (pinfunction "MOSI_17") (pintype "bidirectional"))
    )
    (net (code "64") (name "unconnected-(U1-NC-Pad14)") (class "Default")
      (node (ref "U1") (pin "14") (pinfunction "NC_14") (pintype "bidirectional"))
    )
    (net (code "65") (name "unconnected-(U1-PCM_CLK-Pad5)") (class "Default")
      (node (ref "U1") (pin "5") (pinfunction "PCM_CLK_5") (pintype "bidirectional"))
    )
    (net (code "66") (name "unconnected-(U1-PCM_IN-Pad7)") (class "Default")
      (node (ref "U1") (pin "7") (pinfunction "PCM_IN_7") (pintype "bidirectional"))
    )
    (net (code "67") (name "unconnected-(U1-PCM_OUT-Pad6)") (class "Default")
      (node (ref "U1") (pin "6") (pinfunction "PCM_OUT_6") (pintype "bidirectional"))
    )
    (net (code "68") (name "unconnected-(U1-PCN_SYNC-Pad8)") (class "Default")
      (node (ref "U1") (pin "8") (pinfunction "PCN_SYNC_8") (pintype "bidirectional"))
    )
    (net (code "69") (name "unconnected-(U1-PIO0-Pad23)") (class "Default")
      (node (ref "U1") (pin "23") (pinfunction "PIO0_23") (pintype "bidirectional"))
    )
    (net (code "70") (name "unconnected-(U1-PIO1-Pad24)") (class "Default")
      (node (ref "U1") (pin "24") (pinfunction "PIO1_24") (pintype "bidirectional"))
    )
    (net (code "71") (name "unconnected-(U1-PIO2-Pad25)") (class "Default")
      (node (ref "U1") (pin "25") (pinfunction "PIO2_25") (pintype "bidirectional"))
    )
    (net (code "72") (name "unconnected-(U1-PIO3-Pad26)") (class "Default")
      (node (ref "U1") (pin "26") (pinfunction "PIO3_26") (pintype "bidirectional"))
    )
    (net (code "73") (name "unconnected-(U1-PIO4-Pad27)") (class "Default")
      (node (ref "U1") (pin "27") (pinfunction "PIO4_27") (pintype "bidirectional"))
    )
    (net (code "74") (name "unconnected-(U1-PIO5-Pad28)") (class "Default")
      (node (ref "U1") (pin "28") (pinfunction "PIO5_28") (pintype "bidirectional"))
    )
    (net (code "75") (name "unconnected-(U1-PIO6-Pad29)") (class "Default")
      (node (ref "U1") (pin "29") (pinfunction "PIO6_29") (pintype "bidirectional"))
    )
    (net (code "76") (name "unconnected-(U1-PIO7-Pad30)") (class "Default")
      (node (ref "U1") (pin "30") (pinfunction "PIO7_30") (pintype "bidirectional"))
    )
    (net (code "77") (name "unconnected-(U1-PIO9-Pad32)") (class "Default")
      (node (ref "U1") (pin "32") (pinfunction "PIO9_32") (pintype "bidirectional"))
    )
    (net (code "78") (name "unconnected-(U1-PIO10-Pad33)") (class "Default")
      (node (ref "U1") (pin "33") (pinfunction "PIO10_33") (pintype "bidirectional"))
    )
    (net (code "79") (name "unconnected-(U1-RST-Pad11)") (class "Default")
      (node (ref "U1") (pin "11") (pinfunction "RST_11") (pintype "bidirectional"))
    )
    (net (code "80") (name "unconnected-(U1-RTS-Pad4)") (class "Default")
      (node (ref "U1") (pin "4") (pinfunction "RTS_4") (pintype "bidirectional"))
    )
    (net (code "81") (name "unconnected-(U1-VBUSD+-Pad20)") (class "Default")
      (node (ref "U1") (pin "20") (pinfunction "VBUSD+_20") (pintype "bidirectional"))
    )
    (net (code "82") (name "unconnected-(U1-VBUSD--Pad15)") (class "Default")
      (node (ref "U1") (pin "15") (pinfunction "VBUSD-_15") (pintype "bidirectional"))
    )
    (net (code "83") (name "unconnected-(U2-PA3-Pad17)") (class "Default")
      (node (ref "U2") (pin "17") (pinfunction "PA3_17") (pintype "bidirectional"))
    )
    (net (code "84") (name "unconnected-(U2-PA4-Pad20)") (class "Default")
      (node (ref "U2") (pin "20") (pinfunction "PA4_20") (pintype "bidirectional"))
    )
    (net (code "85") (name "unconnected-(U2-PA5-Pad21)") (class "Default")
      (node (ref "U2") (pin "21") (pinfunction "PA5_21") (pintype "bidirectional"))
    )
    (net (code "86") (name "unconnected-(U2-PA6-Pad22)") (class "Default")
      (node (ref "U2") (pin "22") (pinfunction "PA6_22") (pintype "bidirectional"))
    )
    (net (code "87") (name "unconnected-(U2-PA7-Pad23)") (class "Default")
      (node (ref "U2") (pin "23") (pinfunction "PA7_23") (pintype "bidirectional"))
    )
    (net (code "88") (name "unconnected-(U2-PA8-Pad41)") (class "Default")
      (node (ref "U2") (pin "41") (pinfunction "PA8_41") (pintype "bidirectional"))
    )
    (net (code "89") (name "unconnected-(U2-PA10-Pad43)") (class "Default")
      (node (ref "U2") (pin "43") (pinfunction "PA10_43") (pintype "bidirectional"))
    )
    (net (code "90") (name "unconnected-(U2-PA15-Pad50)") (class "Default")
      (node (ref "U2") (pin "50") (pinfunction "PA15_50") (pintype "bidirectional"))
    )
    (net (code "91") (name "unconnected-(U2-PB0-Pad26)") (class "Default")
      (node (ref "U2") (pin "26") (pinfunction "PB0_26") (pintype "bidirectional"))
    )
    (net (code "92") (name "unconnected-(U2-PB1-Pad27)") (class "Default")
      (node (ref "U2") (pin "27") (pinfunction "PB1_27") (pintype "bidirectional"))
    )
    (net (code "93") (name "unconnected-(U2-PB3-Pad55)") (class "Default")
      (node (ref "U2") (pin "55") (pinfunction "PB3_55") (pintype "bidirectional"))
    )
    (net (code "94") (name "unconnected-(U2-PB4-Pad56)") (class "Default")
      (node (ref "U2") (pin "56") (pinfunction "PB4_56") (pintype "bidirectional"))
    )
    (net (code "95") (name "unconnected-(U2-PB5-Pad57)") (class "Default")
      (node (ref "U2") (pin "57") (pinfunction "PB5_57") (pintype "bidirectional"))
    )
    (net (code "96") (name "unconnected-(U2-PB14-Pad35)") (class "Default")
      (node (ref "U2") (pin "35") (pinfunction "PB14_35") (pintype "bidirectional"))
    )
    (net (code "97") (name "unconnected-(U2-PC0-Pad8)") (class "Default")
      (node (ref "U2") (pin "8") (pinfunction "PC0_8") (pintype "bidirectional"))
    )
    (net (code "98") (name "unconnected-(U2-PC1-Pad9)") (class "Default")
      (node (ref "U2") (pin "9") (pinfunction "PC1_9") (pintype "bidirectional"))
    )
    (net (code "99") (name "unconnected-(U2-PC2-Pad10)") (class "Default")
      (node (ref "U2") (pin "10") (pinfunction "PC2_10") (pintype "bidirectional"))
    )
    (net (code "100") (name "unconnected-(U2-PC3-Pad11)") (class "Default")
      (node (ref "U2") (pin "11") (pinfunction "PC3_11") (pintype "bidirectional"))
    )
    (net (code "101") (name "unconnected-(U2-PC4-Pad24)") (class "Default")
      (node (ref "U2") (pin "24") (pinfunction "PC4_24") (pintype "bidirectional"))
    )
    (net (code "102") (name "unconnected-(U2-PC5-Pad25)") (class "Default")
      (node (ref "U2") (pin "25") (pinfunction "PC5_25") (pintype "bidirectional"))
    )
    (net (code "103") (name "unconnected-(U2-PC6-Pad37)") (class "Default")
      (node (ref "U2") (pin "37") (pinfunction "PC6_37") (pintype "bidirectional"))
    )
    (net (code "104") (name "unconnected-(U2-PC7-Pad38)") (class "Default")
      (node (ref "U2") (pin "38") (pinfunction "PC7_38") (pintype "bidirectional"))
    )
    (net (code "105") (name "unconnected-(U2-PC13-Pad2)") (class "Default")
      (node (ref "U2") (pin "2") (pinfunction "PC13_2") (pintype "bidirectional"))
    )
    (net (code "106") (name "unconnected-(U2-PC14-Pad3)") (class "Default")
      (node (ref "U2") (pin "3") (pinfunction "PC14_3") (pintype "bidirectional"))
    )
    (net (code "107") (name "unconnected-(U2-PC15-Pad4)") (class "Default")
      (node (ref "U2") (pin "4") (pinfunction "PC15_4") (pintype "bidirectional"))
    )
    (net (code "108") (name "unconnected-(U2-USB_DM(PA11)-Pad44)") (class "Default")
      (node (ref "U2") (pin "44") (pinfunction "USB_DM(PA11)_44") (pintype "bidirectional"))
    )
    (net (code "109") (name "unconnected-(U2-USB_DP(PA12)-Pad45)") (class "Default")
      (node (ref "U2") (pin "45") (pinfunction "USB_DP(PA12)_45") (pintype "bidirectional"))
    )
  )
)
